# SCH_beancounter.net
KiCad netlist of a schematic drawn in EasyEDA
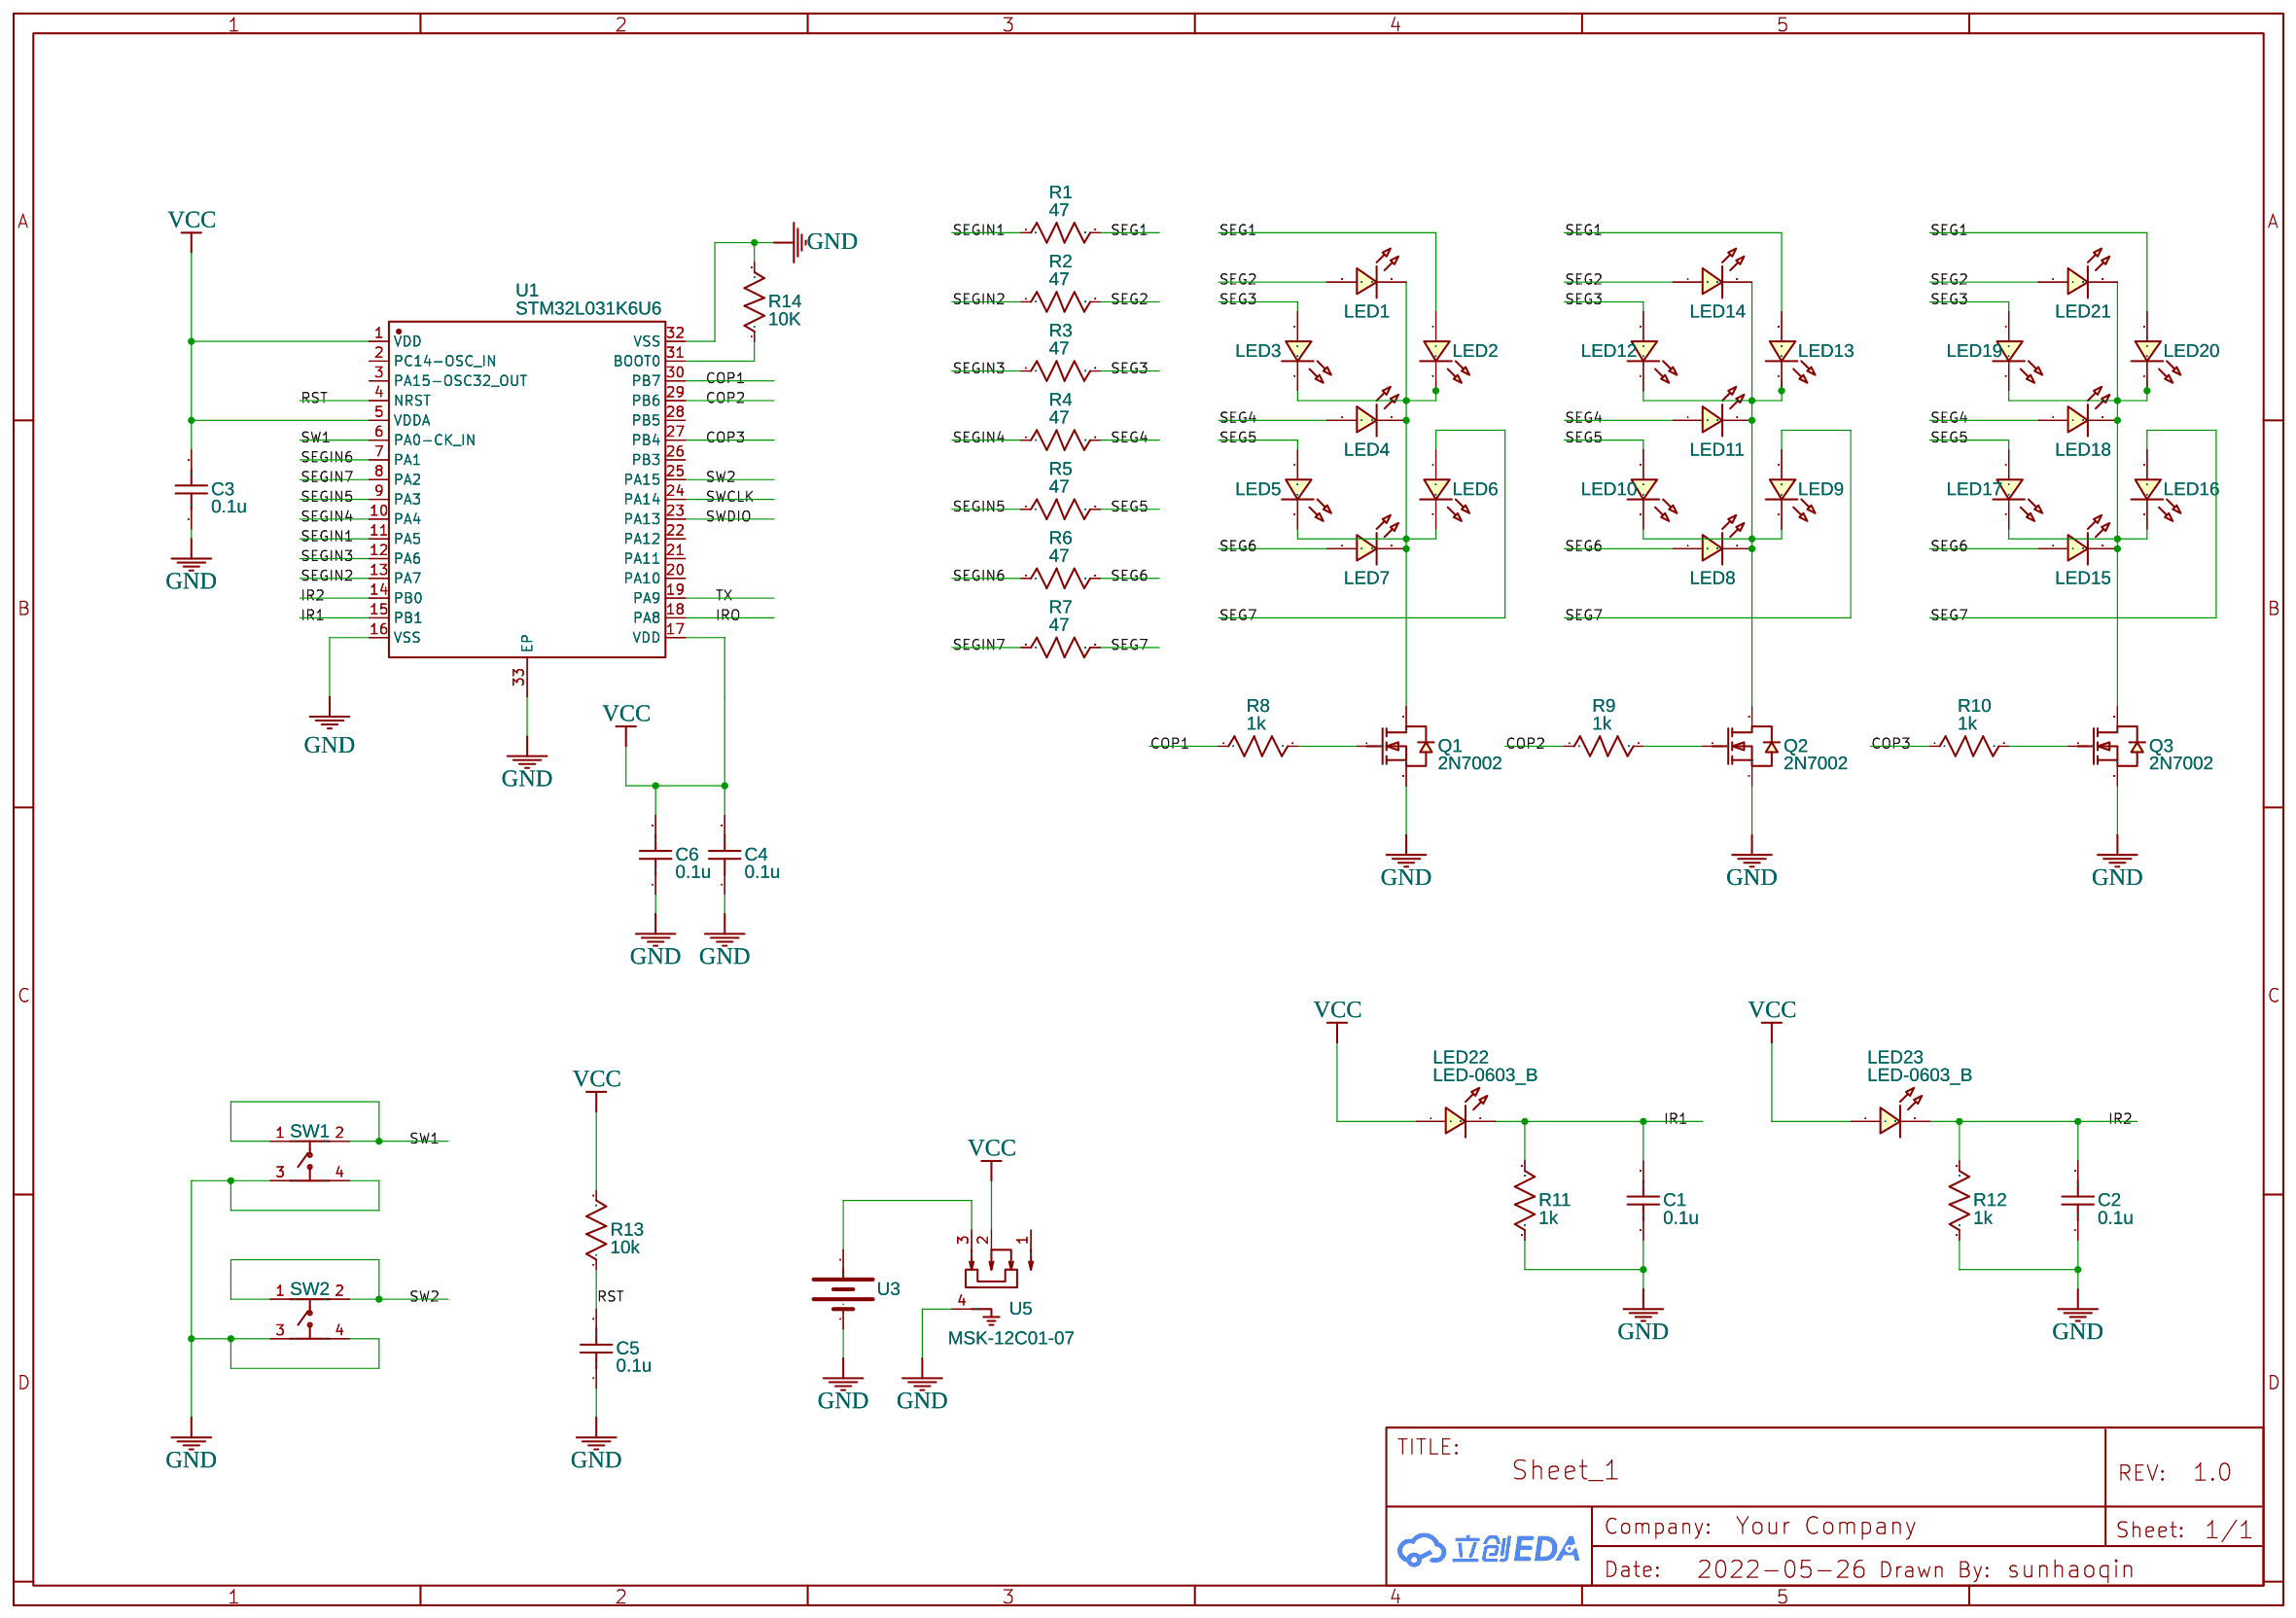
[diagram p0: schematic sheet]

(export (version "E")
  (design (tool "Eeschema 10.0.6"))
  (components
    (comp (ref "C1") (value "0.1u") (libsource (lib "") (part "C_0603_US")))
    (comp (ref "C2") (value "0.1u") (libsource (lib "") (part "C_0603_US")))
    (comp (ref "C3") (value "0.1u") (libsource (lib "") (part "C_0603_US")))
    (comp (ref "C4") (value "0.1u") (libsource (lib "") (part "C_0603_US")))
    (comp (ref "C5") (value "0.1u") (libsource (lib "") (part "C_0603_US")))
    (comp (ref "C6") (value "0.1u") (libsource (lib "") (part "C_0603_US")))
    (comp (ref "LED1")
      (value "LED-0603_B")
      (fields
        (field (name "BOM_Manufacturer Part") "19-217/BHC-ZL1M2RY/3T")
        (field (name "BOM_Supplier Part") "C72041")
      )
      (libsource (lib "") (part "LED-0603_B_1"))
    )
    (comp (ref "LED2")
      (value "LED-0603_B")
      (fields
        (field (name "BOM_Manufacturer Part") "19-217/BHC-ZL1M2RY/3T")
        (field (name "BOM_Supplier Part") "C72041")
      )
      (libsource (lib "") (part "LED-0603_B"))
    )
    (comp (ref "LED3")
      (value "LED-0603_B")
      (fields
        (field (name "BOM_Manufacturer Part") "19-217/BHC-ZL1M2RY/3T")
        (field (name "BOM_Supplier Part") "C72041")
      )
      (libsource (lib "") (part "LED-0603_B"))
    )
    (comp (ref "LED4")
      (value "LED-0603_B")
      (fields
        (field (name "BOM_Manufacturer Part") "19-217/BHC-ZL1M2RY/3T")
        (field (name "BOM_Supplier Part") "C72041")
      )
      (libsource (lib "") (part "LED-0603_B_1"))
    )
    (comp (ref "LED5")
      (value "LED-0603_B")
      (fields
        (field (name "BOM_Manufacturer Part") "19-217/BHC-ZL1M2RY/3T")
        (field (name "BOM_Supplier Part") "C72041")
      )
      (libsource (lib "") (part "LED-0603_B"))
    )
    (comp (ref "LED6")
      (value "LED-0603_B")
      (fields
        (field (name "BOM_Manufacturer Part") "19-217/BHC-ZL1M2RY/3T")
        (field (name "BOM_Supplier Part") "C72041")
      )
      (libsource (lib "") (part "LED-0603_B"))
    )
    (comp (ref "LED7")
      (value "LED-0603_B")
      (fields
        (field (name "BOM_Manufacturer Part") "19-217/BHC-ZL1M2RY/3T")
        (field (name "BOM_Supplier Part") "C72041")
      )
      (libsource (lib "") (part "LED-0603_B_1"))
    )
    (comp (ref "LED8")
      (value "LED-0603_B")
      (fields
        (field (name "BOM_Manufacturer Part") "19-217/BHC-ZL1M2RY/3T")
        (field (name "BOM_Supplier Part") "C72041")
      )
      (libsource (lib "") (part "LED-0603_B_1"))
    )
    (comp (ref "LED9")
      (value "LED-0603_B")
      (fields
        (field (name "BOM_Manufacturer Part") "19-217/BHC-ZL1M2RY/3T")
        (field (name "BOM_Supplier Part") "C72041")
      )
      (libsource (lib "") (part "LED-0603_B"))
    )
    (comp (ref "LED10")
      (value "LED-0603_B")
      (fields
        (field (name "BOM_Manufacturer Part") "19-217/BHC-ZL1M2RY/3T")
        (field (name "BOM_Supplier Part") "C72041")
      )
      (libsource (lib "") (part "LED-0603_B"))
    )
    (comp (ref "LED11")
      (value "LED-0603_B")
      (fields
        (field (name "BOM_Manufacturer Part") "19-217/BHC-ZL1M2RY/3T")
        (field (name "BOM_Supplier Part") "C72041")
      )
      (libsource (lib "") (part "LED-0603_B_1"))
    )
    (comp (ref "LED12")
      (value "LED-0603_B")
      (fields
        (field (name "BOM_Manufacturer Part") "19-217/BHC-ZL1M2RY/3T")
        (field (name "BOM_Supplier Part") "C72041")
      )
      (libsource (lib "") (part "LED-0603_B"))
    )
    (comp (ref "LED13")
      (value "LED-0603_B")
      (fields
        (field (name "BOM_Manufacturer Part") "19-217/BHC-ZL1M2RY/3T")
        (field (name "BOM_Supplier Part") "C72041")
      )
      (libsource (lib "") (part "LED-0603_B"))
    )
    (comp (ref "LED14")
      (value "LED-0603_B")
      (fields
        (field (name "BOM_Manufacturer Part") "19-217/BHC-ZL1M2RY/3T")
        (field (name "BOM_Supplier Part") "C72041")
      )
      (libsource (lib "") (part "LED-0603_B_1"))
    )
    (comp (ref "LED15")
      (value "LED-0603_B")
      (fields
        (field (name "BOM_Manufacturer Part") "19-217/BHC-ZL1M2RY/3T")
        (field (name "BOM_Supplier Part") "C72041")
      )
      (libsource (lib "") (part "LED-0603_B_1"))
    )
    (comp (ref "LED16")
      (value "LED-0603_B")
      (fields
        (field (name "BOM_Manufacturer Part") "19-217/BHC-ZL1M2RY/3T")
        (field (name "BOM_Supplier Part") "C72041")
      )
      (libsource (lib "") (part "LED-0603_B"))
    )
    (comp (ref "LED17")
      (value "LED-0603_B")
      (fields
        (field (name "BOM_Manufacturer Part") "19-217/BHC-ZL1M2RY/3T")
        (field (name "BOM_Supplier Part") "C72041")
      )
      (libsource (lib "") (part "LED-0603_B"))
    )
    (comp (ref "LED18")
      (value "LED-0603_B")
      (fields
        (field (name "BOM_Manufacturer Part") "19-217/BHC-ZL1M2RY/3T")
        (field (name "BOM_Supplier Part") "C72041")
      )
      (libsource (lib "") (part "LED-0603_B_1"))
    )
    (comp (ref "LED19")
      (value "LED-0603_B")
      (fields
        (field (name "BOM_Manufacturer Part") "19-217/BHC-ZL1M2RY/3T")
        (field (name "BOM_Supplier Part") "C72041")
      )
      (libsource (lib "") (part "LED-0603_B"))
    )
    (comp (ref "LED20")
      (value "LED-0603_B")
      (fields
        (field (name "BOM_Manufacturer Part") "19-217/BHC-ZL1M2RY/3T")
        (field (name "BOM_Supplier Part") "C72041")
      )
      (libsource (lib "") (part "LED-0603_B"))
    )
    (comp (ref "LED21")
      (value "LED-0603_B")
      (fields
        (field (name "BOM_Manufacturer Part") "19-217/BHC-ZL1M2RY/3T")
        (field (name "BOM_Supplier Part") "C72041")
      )
      (libsource (lib "") (part "LED-0603_B_1"))
    )
    (comp (ref "LED22")
      (value "LED-0603_B")
      (fields
        (field (name "BOM_Manufacturer Part") "19-217/BHC-ZL1M2RY/3T")
        (field (name "BOM_Supplier Part") "C72041")
      )
      (libsource (lib "") (part "LED-0603_B_1"))
    )
    (comp (ref "LED23")
      (value "LED-0603_B")
      (fields
        (field (name "BOM_Manufacturer Part") "19-217/BHC-ZL1M2RY/3T")
        (field (name "BOM_Supplier Part") "C72041")
      )
      (libsource (lib "") (part "LED-0603_B_1"))
    )
    (comp (ref "Q1")
      (value "2N7002")
      (fields (field (name "BOM_Manufacturer Part") "2N7002,215") (field (name "BOM_Supplier Part") "C65189"))
      (libsource (lib "") (part "2N7002"))
    )
    (comp (ref "Q2")
      (value "2N7002")
      (fields (field (name "BOM_Manufacturer Part") "2N7002,215") (field (name "BOM_Supplier Part") "C65189"))
      (libsource (lib "") (part "2N7002"))
    )
    (comp (ref "Q3")
      (value "2N7002")
      (fields (field (name "BOM_Manufacturer Part") "2N7002,215") (field (name "BOM_Supplier Part") "C65189"))
      (libsource (lib "") (part "2N7002"))
    )
    (comp (ref "R1") (value "47") (libsource (lib "") (part "R_0603_US_1")))
    (comp (ref "R2") (value "47") (libsource (lib "") (part "R_0603_US_1")))
    (comp (ref "R3") (value "47") (libsource (lib "") (part "R_0603_US_1")))
    (comp (ref "R4") (value "47") (libsource (lib "") (part "R_0603_US_1")))
    (comp (ref "R5") (value "47") (libsource (lib "") (part "R_0603_US_1")))
    (comp (ref "R6") (value "47") (libsource (lib "") (part "R_0603_US_1")))
    (comp (ref "R7") (value "47") (libsource (lib "") (part "R_0603_US_1")))
    (comp (ref "R8") (value "1k") (libsource (lib "") (part "R_0603_US_1")))
    (comp (ref "R9") (value "1k") (libsource (lib "") (part "R_0603_US_1")))
    (comp (ref "R10") (value "1k") (libsource (lib "") (part "R_0603_US_1")))
    (comp (ref "R11") (value "1k") (libsource (lib "") (part "R_0603_US")))
    (comp (ref "R12") (value "1k") (libsource (lib "") (part "R_0603_US")))
    (comp (ref "R13") (value "10k") (libsource (lib "") (part "R_0603_US")))
    (comp (ref "R14") (value "10K") (libsource (lib "") (part "R_0603_US")))
    (comp (ref "SW1")
      (value "TSC005B1526A")
      (fields (field (name "BOM_Supplier Part") "C2888895"))
      (libsource (lib "") (part "TSC005B1526A"))
    )
    (comp (ref "SW2")
      (value "TSC005B1526A")
      (fields (field (name "BOM_Supplier Part") "C2888895"))
      (libsource (lib "") (part "TSC005B1526A"))
    )
    (comp (ref "U1")
      (value "STM32L031K6U6")
      (fields (field (name "BOM_Supplier Part") "C967648"))
      (libsource (lib "") (part "STM32L031K6U6"))
    )
    (comp (ref "U3")
      (value "CR2032-卧式贴片JACOB")
      (fields
        (field (name "BOM_Manufacturer Part") "CR2032-卧式贴片")
        (field (name "BOM_Supplier Part") "C9900005595")
      )
      (libsource (lib "") (part "CR2032-卧式贴片JACOB"))
    )
    (comp (ref "U5")
      (value "MSK-12C01-07")
      (fields (field (name "BOM_Supplier Part") "C9900005167"))
      (libsource (lib "") (part "MSK-12C01-07"))
    )
  )
  (nets
    (net (code "1") (name "/COP1") (class "Default")
      (node (ref "R8") (pin "1") (pinfunction "1_1") (pintype "unspecified"))
      (node (ref "U1") (pin "30") (pinfunction "PB7_30") (pintype "unspecified"))
    )
    (net (code "2") (name "/COP2") (class "Default")
      (node (ref "R9") (pin "1") (pinfunction "1_1") (pintype "unspecified"))
      (node (ref "U1") (pin "29") (pinfunction "PB6_29") (pintype "unspecified"))
    )
    (net (code "3") (name "/COP3") (class "Default")
      (node (ref "R10") (pin "1") (pinfunction "1_1") (pintype "unspecified"))
      (node (ref "U1") (pin "27") (pinfunction "PB4_27") (pintype "unspecified"))
    )
    (net (code "4") (name "/IR1") (class "Default")
      (node (ref "C1") (pin "2") (pinfunction "2_2") (pintype "unspecified"))
      (node (ref "LED22") (pin "2") (pinfunction "2_2") (pintype "unspecified"))
      (node (ref "R11") (pin "2") (pinfunction "2_2") (pintype "unspecified"))
      (node (ref "U1") (pin "15") (pinfunction "PB1_15") (pintype "unspecified"))
    )
    (net (code "5") (name "/IR2") (class "Default")
      (node (ref "C2") (pin "2") (pinfunction "2_2") (pintype "unspecified"))
      (node (ref "LED23") (pin "2") (pinfunction "2_2") (pintype "unspecified"))
      (node (ref "R12") (pin "2") (pinfunction "2_2") (pintype "unspecified"))
      (node (ref "U1") (pin "14") (pinfunction "PB0_14") (pintype "unspecified"))
    )
    (net (code "6") (name "/IRO") (class "Default")
      (node (ref "U1") (pin "18") (pinfunction "PA8_18") (pintype "unspecified"))
    )
    (net (code "7") (name "/RST") (class "Default")
      (node (ref "C5") (pin "2") (pinfunction "2_2") (pintype "unspecified"))
      (node (ref "R13") (pin "1") (pinfunction "1_1") (pintype "unspecified"))
      (node (ref "U1") (pin "4") (pinfunction "NRST_4") (pintype "unspecified"))
    )
    (net (code "8") (name "/SEG1") (class "Default")
      (node (ref "LED13") (pin "1") (pinfunction "1_1") (pintype "unspecified"))
      (node (ref "LED2") (pin "1") (pinfunction "1_1") (pintype "unspecified"))
      (node (ref "LED20") (pin "1") (pinfunction "1_1") (pintype "unspecified"))
      (node (ref "R1") (pin "2") (pinfunction "2_2") (pintype "unspecified"))
    )
    (net (code "9") (name "/SEG2") (class "Default")
      (node (ref "LED1") (pin "1") (pinfunction "1_1") (pintype "unspecified"))
      (node (ref "LED14") (pin "1") (pinfunction "1_1") (pintype "unspecified"))
      (node (ref "LED21") (pin "1") (pinfunction "1_1") (pintype "unspecified"))
      (node (ref "R2") (pin "2") (pinfunction "2_2") (pintype "unspecified"))
    )
    (net (code "10") (name "/SEG3") (class "Default")
      (node (ref "LED12") (pin "1") (pinfunction "1_1") (pintype "unspecified"))
      (node (ref "LED19") (pin "1") (pinfunction "1_1") (pintype "unspecified"))
      (node (ref "LED3") (pin "1") (pinfunction "1_1") (pintype "unspecified"))
      (node (ref "R3") (pin "2") (pinfunction "2_2") (pintype "unspecified"))
    )
    (net (code "11") (name "/SEG4") (class "Default")
      (node (ref "LED11") (pin "1") (pinfunction "1_1") (pintype "unspecified"))
      (node (ref "LED18") (pin "1") (pinfunction "1_1") (pintype "unspecified"))
      (node (ref "LED4") (pin "1") (pinfunction "1_1") (pintype "unspecified"))
      (node (ref "R4") (pin "2") (pinfunction "2_2") (pintype "unspecified"))
    )
    (net (code "12") (name "/SEG5") (class "Default")
      (node (ref "LED10") (pin "1") (pinfunction "1_1") (pintype "unspecified"))
      (node (ref "LED17") (pin "1") (pinfunction "1_1") (pintype "unspecified"))
      (node (ref "LED5") (pin "1") (pinfunction "1_1") (pintype "unspecified"))
      (node (ref "R5") (pin "2") (pinfunction "2_2") (pintype "unspecified"))
    )
    (net (code "13") (name "/SEG6") (class "Default")
      (node (ref "LED15") (pin "1") (pinfunction "1_1") (pintype "unspecified"))
      (node (ref "LED7") (pin "1") (pinfunction "1_1") (pintype "unspecified"))
      (node (ref "LED8") (pin "1") (pinfunction "1_1") (pintype "unspecified"))
      (node (ref "R6") (pin "2") (pinfunction "2_2") (pintype "unspecified"))
    )
    (net (code "14") (name "/SEG7") (class "Default")
      (node (ref "LED16") (pin "1") (pinfunction "1_1") (pintype "unspecified"))
      (node (ref "LED6") (pin "1") (pinfunction "1_1") (pintype "unspecified"))
      (node (ref "LED9") (pin "1") (pinfunction "1_1") (pintype "unspecified"))
      (node (ref "R7") (pin "2") (pinfunction "2_2") (pintype "unspecified"))
    )
    (net (code "15") (name "/SEGIN1") (class "Default")
      (node (ref "R1") (pin "1") (pinfunction "1_1") (pintype "unspecified"))
      (node (ref "U1") (pin "11") (pinfunction "PA5_11") (pintype "unspecified"))
    )
    (net (code "16") (name "/SEGIN2") (class "Default")
      (node (ref "R2") (pin "1") (pinfunction "1_1") (pintype "unspecified"))
      (node (ref "U1") (pin "13") (pinfunction "PA7_13") (pintype "unspecified"))
    )
    (net (code "17") (name "/SEGIN3") (class "Default")
      (node (ref "R3") (pin "1") (pinfunction "1_1") (pintype "unspecified"))
      (node (ref "U1") (pin "12") (pinfunction "PA6_12") (pintype "unspecified"))
    )
    (net (code "18") (name "/SEGIN4") (class "Default")
      (node (ref "R4") (pin "1") (pinfunction "1_1") (pintype "unspecified"))
      (node (ref "U1") (pin "10") (pinfunction "PA4_10") (pintype "unspecified"))
    )
    (net (code "19") (name "/SEGIN5") (class "Default")
      (node (ref "R5") (pin "1") (pinfunction "1_1") (pintype "unspecified"))
      (node (ref "U1") (pin "9") (pinfunction "PA3_9") (pintype "unspecified"))
    )
    (net (code "20") (name "/SEGIN6") (class "Default")
      (node (ref "R6") (pin "1") (pinfunction "1_1") (pintype "unspecified"))
      (node (ref "U1") (pin "7") (pinfunction "PA1_7") (pintype "unspecified"))
    )
    (net (code "21") (name "/SEGIN7") (class "Default")
      (node (ref "R7") (pin "1") (pinfunction "1_1") (pintype "unspecified"))
      (node (ref "U1") (pin "8") (pinfunction "PA2_8") (pintype "unspecified"))
    )
    (net (code "22") (name "/SW1") (class "Default")
      (node (ref "SW1") (pin "1") (pinfunction "1_1") (pintype "unspecified"))
      (node (ref "SW1") (pin "2") (pinfunction "2_2") (pintype "unspecified"))
      (node (ref "U1") (pin "6") (pinfunction "PA0-CK_IN_6") (pintype "unspecified"))
    )
    (net (code "23") (name "/SW2") (class "Default")
      (node (ref "SW2") (pin "1") (pinfunction "1_1") (pintype "unspecified"))
      (node (ref "SW2") (pin "2") (pinfunction "2_2") (pintype "unspecified"))
      (node (ref "U1") (pin "25") (pinfunction "PA15_25") (pintype "unspecified"))
    )
    (net (code "24") (name "/SWCLK") (class "Default")
      (node (ref "U1") (pin "24") (pinfunction "PA14_24") (pintype "unspecified"))
    )
    (net (code "25") (name "/SWDIO") (class "Default")
      (node (ref "U1") (pin "23") (pinfunction "PA13_23") (pintype "unspecified"))
    )
    (net (code "26") (name "/TX") (class "Default")
      (node (ref "U1") (pin "19") (pinfunction "PA9_19") (pintype "unspecified"))
    )
    (net (code "27") (name "GND") (class "Default")
      (node (ref "C1") (pin "1") (pinfunction "1_1") (pintype "unspecified"))
      (node (ref "C2") (pin "1") (pinfunction "1_1") (pintype "unspecified"))
      (node (ref "C3") (pin "1") (pinfunction "1_1") (pintype "unspecified"))
      (node (ref "C4") (pin "1") (pinfunction "1_1") (pintype "unspecified"))
      (node (ref "C5") (pin "1") (pinfunction "1_1") (pintype "unspecified"))
      (node (ref "C6") (pin "1") (pinfunction "1_1") (pintype "unspecified"))
      (node (ref "Q1") (pin "2") (pinfunction "S_2") (pintype "unspecified"))
      (node (ref "Q2") (pin "2") (pinfunction "S_2") (pintype "unspecified"))
      (node (ref "Q3") (pin "2") (pinfunction "S_2") (pintype "unspecified"))
      (node (ref "R11") (pin "1") (pinfunction "1_1") (pintype "unspecified"))
      (node (ref "R12") (pin "1") (pinfunction "1_1") (pintype "unspecified"))
      (node (ref "R14") (pin "2") (pinfunction "2_2") (pintype "unspecified"))
      (node (ref "SW1") (pin "3") (pinfunction "3_3") (pintype "unspecified"))
      (node (ref "SW1") (pin "4") (pinfunction "4_4") (pintype "unspecified"))
      (node (ref "SW2") (pin "3") (pinfunction "3_3") (pintype "unspecified"))
      (node (ref "SW2") (pin "4") (pinfunction "4_4") (pintype "unspecified"))
      (node (ref "U1") (pin "16") (pinfunction "VSS_16") (pintype "unspecified"))
      (node (ref "U1") (pin "32") (pinfunction "VSS_32") (pintype "unspecified"))
      (node (ref "U1") (pin "33") (pinfunction "EP_33") (pintype "unspecified"))
      (node (ref "U3") (pin "1") (pinfunction "-_1") (pintype "passive"))
      (node (ref "U5") (pin "4") (pinfunction "4_4") (pintype "unspecified"))
    )
    (net (code "28") (name "Net-(Q1-D)") (class "Default")
      (node (ref "LED1") (pin "2") (pinfunction "2_2") (pintype "unspecified"))
      (node (ref "LED2") (pin "2") (pinfunction "2_2") (pintype "unspecified"))
      (node (ref "LED3") (pin "2") (pinfunction "2_2") (pintype "unspecified"))
      (node (ref "LED4") (pin "2") (pinfunction "2_2") (pintype "unspecified"))
      (node (ref "LED5") (pin "2") (pinfunction "2_2") (pintype "unspecified"))
      (node (ref "LED6") (pin "2") (pinfunction "2_2") (pintype "unspecified"))
      (node (ref "LED7") (pin "2") (pinfunction "2_2") (pintype "unspecified"))
      (node (ref "Q1") (pin "3") (pinfunction "D_3") (pintype "unspecified"))
    )
    (net (code "29") (name "Net-(Q1-G)") (class "Default")
      (node (ref "Q1") (pin "1") (pinfunction "G_1") (pintype "unspecified"))
      (node (ref "R8") (pin "2") (pinfunction "2_2") (pintype "unspecified"))
    )
    (net (code "30") (name "Net-(Q2-D)") (class "Default")
      (node (ref "LED10") (pin "2") (pinfunction "2_2") (pintype "unspecified"))
      (node (ref "LED11") (pin "2") (pinfunction "2_2") (pintype "unspecified"))
      (node (ref "LED12") (pin "2") (pinfunction "2_2") (pintype "unspecified"))
      (node (ref "LED13") (pin "2") (pinfunction "2_2") (pintype "unspecified"))
      (node (ref "LED14") (pin "2") (pinfunction "2_2") (pintype "unspecified"))
      (node (ref "LED8") (pin "2") (pinfunction "2_2") (pintype "unspecified"))
      (node (ref "LED9") (pin "2") (pinfunction "2_2") (pintype "unspecified"))
      (node (ref "Q2") (pin "3") (pinfunction "D_3") (pintype "unspecified"))
    )
    (net (code "31") (name "Net-(Q2-G)") (class "Default")
      (node (ref "Q2") (pin "1") (pinfunction "G_1") (pintype "unspecified"))
      (node (ref "R9") (pin "2") (pinfunction "2_2") (pintype "unspecified"))
    )
    (net (code "32") (name "Net-(Q3-D)") (class "Default")
      (node (ref "LED15") (pin "2") (pinfunction "2_2") (pintype "unspecified"))
      (node (ref "LED16") (pin "2") (pinfunction "2_2") (pintype "unspecified"))
      (node (ref "LED17") (pin "2") (pinfunction "2_2") (pintype "unspecified"))
      (node (ref "LED18") (pin "2") (pinfunction "2_2") (pintype "unspecified"))
      (node (ref "LED19") (pin "2") (pinfunction "2_2") (pintype "unspecified"))
      (node (ref "LED20") (pin "2") (pinfunction "2_2") (pintype "unspecified"))
      (node (ref "LED21") (pin "2") (pinfunction "2_2") (pintype "unspecified"))
      (node (ref "Q3") (pin "3") (pinfunction "D_3") (pintype "unspecified"))
    )
    (net (code "33") (name "Net-(Q3-G)") (class "Default")
      (node (ref "Q3") (pin "1") (pinfunction "G_1") (pintype "unspecified"))
      (node (ref "R10") (pin "2") (pinfunction "2_2") (pintype "unspecified"))
    )
    (net (code "34") (name "Net-(U1-BOOT0)") (class "Default")
      (node (ref "R14") (pin "1") (pinfunction "1_1") (pintype "unspecified"))
      (node (ref "U1") (pin "31") (pinfunction "BOOT0_31") (pintype "unspecified"))
    )
    (net (code "35") (name "Net-(U3-+)") (class "Default")
      (node (ref "U3") (pin "2") (pinfunction "+_2") (pintype "passive"))
      (node (ref "U5") (pin "3") (pinfunction "3_3") (pintype "unspecified"))
    )
    (net (code "36") (name "VCC") (class "Default")
      (node (ref "C3") (pin "2") (pinfunction "2_2") (pintype "unspecified"))
      (node (ref "C4") (pin "2") (pinfunction "2_2") (pintype "unspecified"))
      (node (ref "C6") (pin "2") (pinfunction "2_2") (pintype "unspecified"))
      (node (ref "LED22") (pin "1") (pinfunction "1_1") (pintype "unspecified"))
      (node (ref "LED23") (pin "1") (pinfunction "1_1") (pintype "unspecified"))
      (node (ref "R13") (pin "2") (pinfunction "2_2") (pintype "unspecified"))
      (node (ref "U1") (pin "1") (pinfunction "VDD_1") (pintype "unspecified"))
      (node (ref "U1") (pin "17") (pinfunction "VDD_17") (pintype "unspecified"))
      (node (ref "U1") (pin "5") (pinfunction "VDDA_5") (pintype "unspecified"))
      (node (ref "U5") (pin "2") (pinfunction "2_2") (pintype "unspecified"))
    )
    (net (code "37") (name "unconnected-(U1-PA10-Pad20)") (class "Default")
      (node (ref "U1") (pin "20") (pinfunction "PA10_20") (pintype "unspecified"))
    )
    (net (code "38") (name "unconnected-(U1-PA11-Pad21)") (class "Default")
      (node (ref "U1") (pin "21") (pinfunction "PA11_21") (pintype "unspecified"))
    )
    (net (code "39") (name "unconnected-(U1-PA12-Pad22)") (class "Default")
      (node (ref "U1") (pin "22") (pinfunction "PA12_22") (pintype "unspecified"))
    )
    (net (code "40") (name "unconnected-(U1-PA15-OSC32_OUT-Pad3)") (class "Default")
      (node (ref "U1") (pin "3") (pinfunction "PA15-OSC32_OUT_3") (pintype "unspecified"))
    )
    (net (code "41") (name "unconnected-(U1-PB3-Pad26)") (class "Default")
      (node (ref "U1") (pin "26") (pinfunction "PB3_26") (pintype "unspecified"))
    )
    (net (code "42") (name "unconnected-(U1-PB5-Pad28)") (class "Default")
      (node (ref "U1") (pin "28") (pinfunction "PB5_28") (pintype "unspecified"))
    )
    (net (code "43") (name "unconnected-(U1-PC14-OSC_IN-Pad2)") (class "Default")
      (node (ref "U1") (pin "2") (pinfunction "PC14-OSC_IN_2") (pintype "unspecified"))
    )
    (net (code "44") (name "unconnected-(U5-Pad1)") (class "Default")
      (node (ref "U5") (pin "1") (pinfunction "1_1") (pintype "unspecified"))
    )
  )
)
